# 05-General_I2C_Devices.net
KiCad netlist of a schematic drawn in Altium Designer
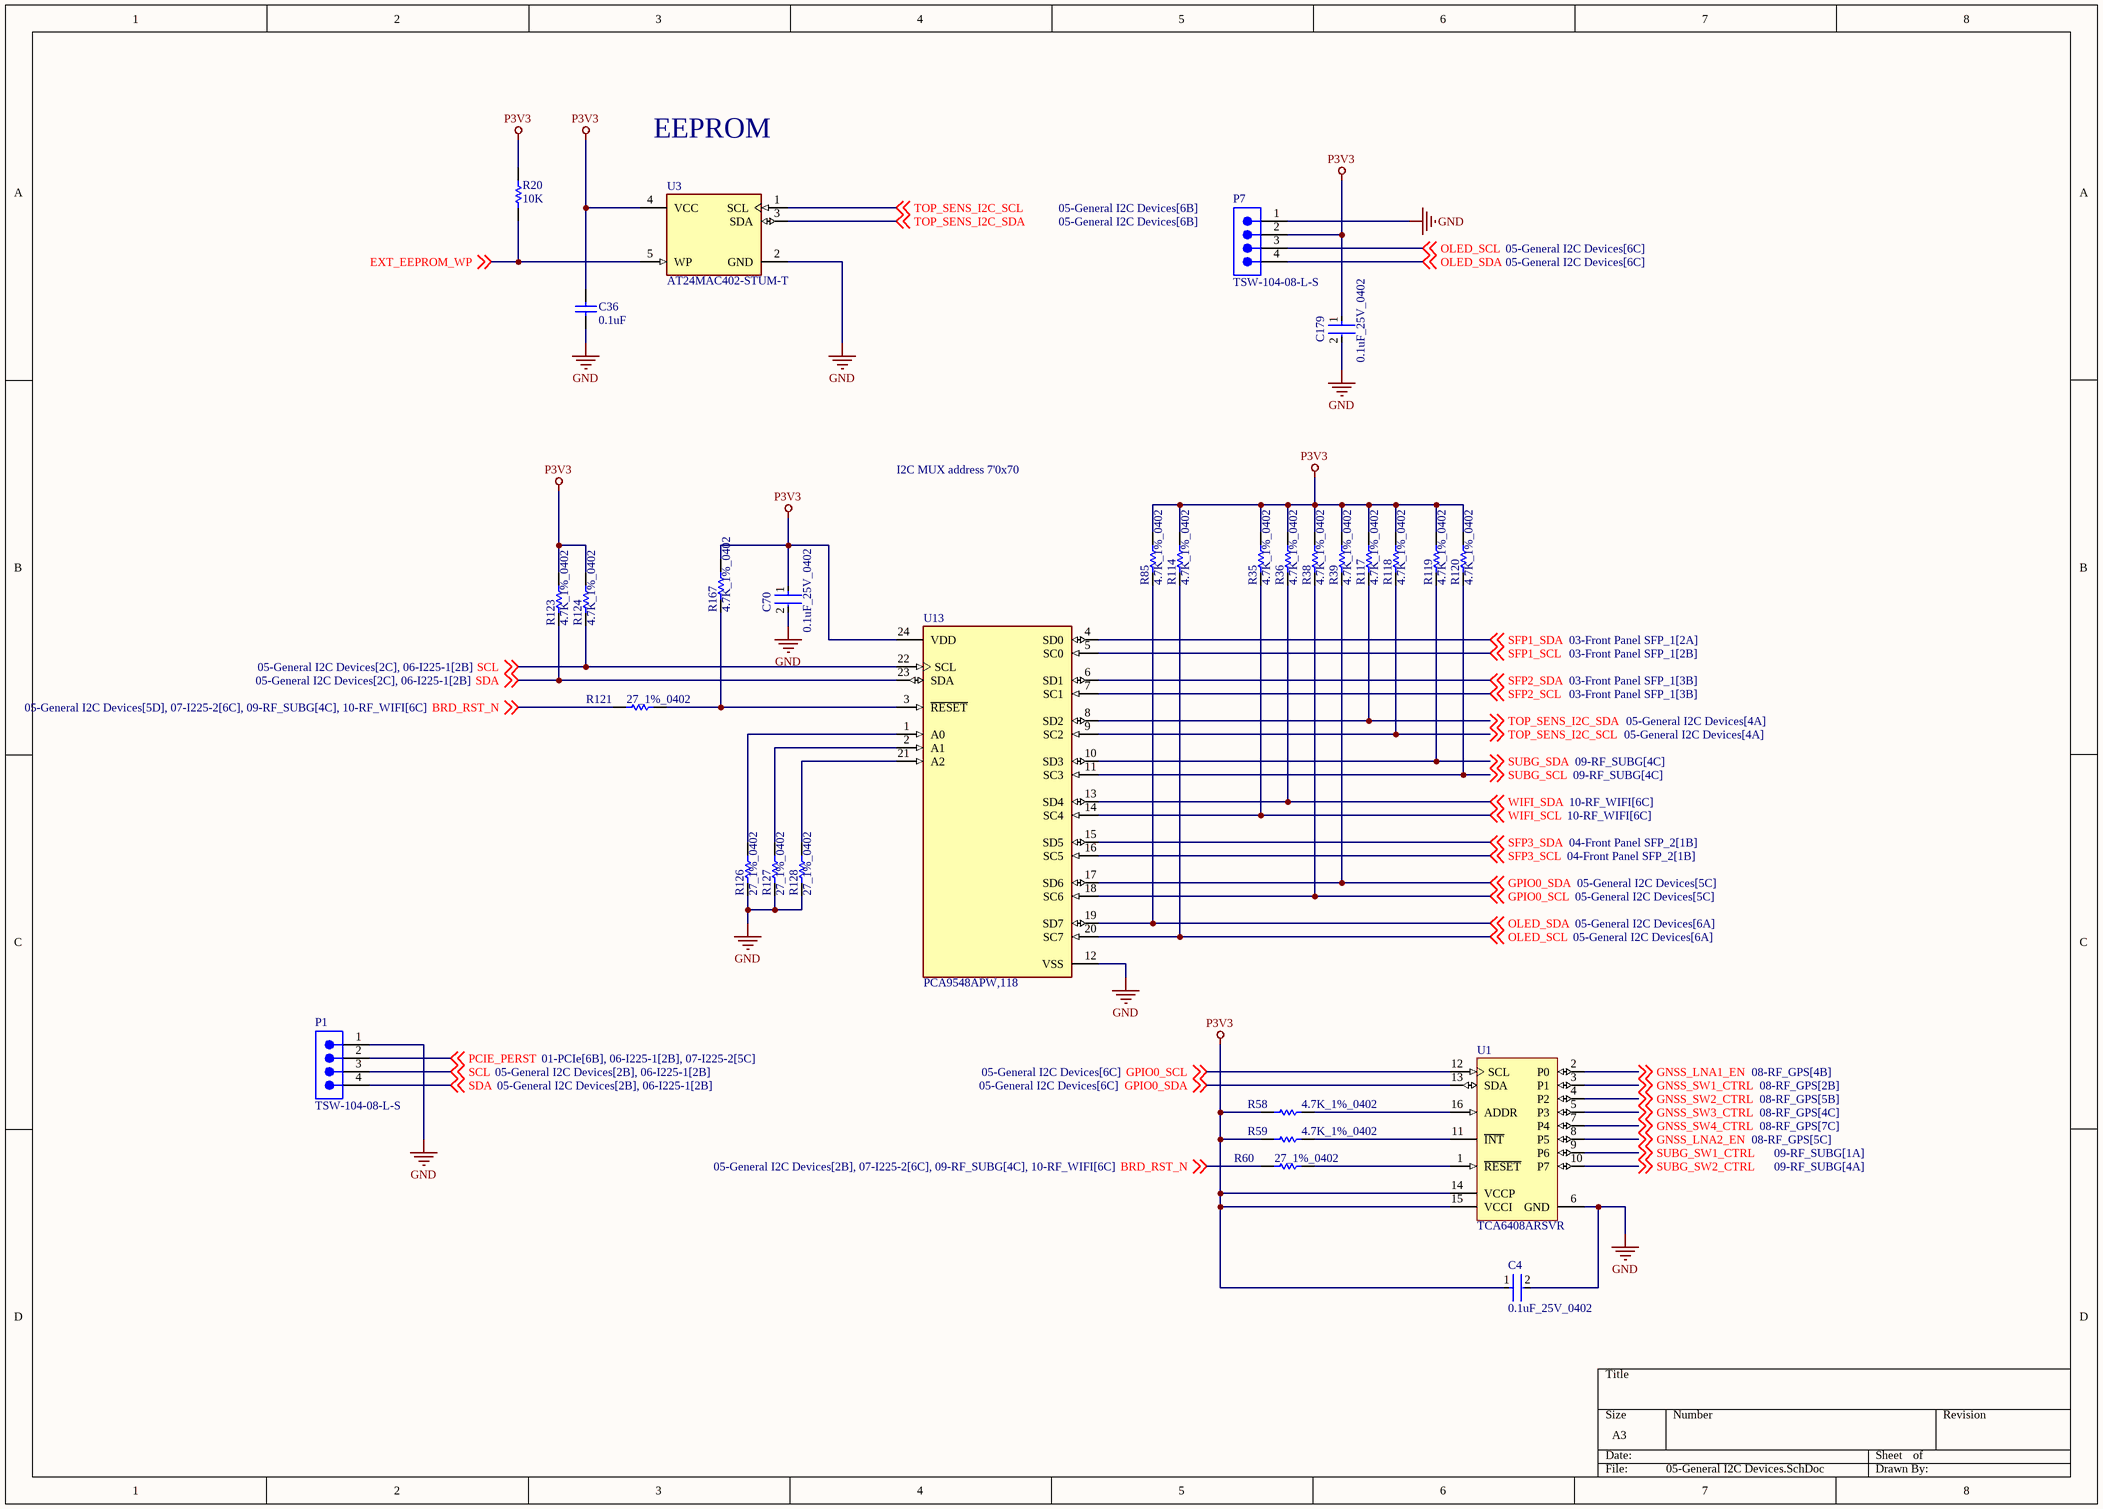
[diagram p0: 05-General I2C Devices.SchDoc]

(export (version "E")
  (design (tool "Eeschema 10.0.6"))
  (components
    (comp (ref "C4")
      (value "0.1uF_25V_0402")
      (footprint "FP-0402-L_1_0_1-W_0_5_0_1-IPC_C")
      (description "General Purpose Ceramic Capacitor, 0402, 100nF, 10%, X7R, 15%, 25V")
      (fields (field (name "VOLTAGE") "25V") (field (name "TOLERANCE") "10%"))
      (libsource (lib "Altium Content Vault") (part "b4654b650e69147ec39a6b967a45e02"))
    )
    (comp (ref "C36")
      (value "0.1uF")
      (footprint "CAPC1608X87X45ML20T05")
      (description "C0603X104K5RACAUTO")
      (fields (field (name "MANUFACTURER") "Kemet"))
      (libsource (lib "Altium Content Vault") (part "CAP"))
    )
    (comp (ref "C70")
      (value "0.1uF_25V_0402")
      (footprint "FP-0402-L_1_0_1-W_0_5_0_1-IPC_C")
      (description "General Purpose Ceramic Capacitor, 0402, 100nF, 10%, X7R, 15%, 25V")
      (fields (field (name "VOLTAGE") "25V") (field (name "TOLERANCE") "10%"))
      (libsource (lib "Altium Content Vault") (part "b4654b650e69147ec39a6b967a45e02"))
    )
    (comp (ref "C179")
      (value "0.1uF_25V_0402")
      (footprint "FP-0402-L_1_0_1-W_0_5_0_1-IPC_C")
      (description "General Purpose Ceramic Capacitor, 0402, 100nF, 10%, X7R, 15%, 25V")
      (fields (field (name "VOLTAGE") "25V") (field (name "TOLERANCE") "10%"))
      (libsource (lib "Altium Content Vault") (part "b4654b650e69147ec39a6b967a45e02"))
    )
    (comp (ref "P1")
      (value "TSW-104-08-L-S")
      (footprint "SMTC-TSW-104-08-X-S")
      (description "0.025\" SQ Post Header, Through-hole, Vertical, -55 to 125 degC, 2.54 mm Pitch, 4-Pin, Male, RoHS")
      (fields (field (name "MANUFACTURER") "Samtec"))
      (libsource (lib "Altium Content Vault") (part "SMTC-TSW-104-08-X-S"))
    )
    (comp (ref "P7")
      (value "TSW-104-08-L-S")
      (footprint "SMTC-TSW-104-08-X-S")
      (description "0.025\" SQ Post Header, Through-hole, Vertical, -55 to 125 degC, 2.54 mm Pitch, 4-Pin, Male, RoHS")
      (fields (field (name "MANUFACTURER") "Samtec"))
      (libsource (lib "Altium Content Vault") (part "SMTC-TSW-104-08-X-S"))
    )
    (comp (ref "R20")
      (value "10K")
      (footprint "RESC1608X55X30LL15T20")
      (fields (field (name "TOLERANCE") "±1%") (field (name "MANUFACTURER") "Stackpole-Electronics-Inc."))
      (libsource (lib "Altium Content Vault") (part "RES-2"))
    )
    (comp (ref "R35")
      (value "4.7K_1%_0402")
      (footprint "RESC1005X40X25NL10T10")
      (fields (field (name "MANUFACTURER") "Bourns") (field (name "PART NUMBER") "CR0402-FX-4701GLF"))
      (libsource (lib "Altium Content Vault") (part "RES"))
    )
    (comp (ref "R36")
      (value "4.7K_1%_0402")
      (footprint "RESC1005X40X25NL10T10")
      (fields (field (name "MANUFACTURER") "Bourns") (field (name "PART NUMBER") "CR0402-FX-4701GLF"))
      (libsource (lib "Altium Content Vault") (part "RES"))
    )
    (comp (ref "R38")
      (value "4.7K_1%_0402")
      (footprint "RESC1005X40X25NL10T10")
      (fields (field (name "MANUFACTURER") "Bourns") (field (name "PART NUMBER") "CR0402-FX-4701GLF"))
      (libsource (lib "Altium Content Vault") (part "RES"))
    )
    (comp (ref "R39")
      (value "4.7K_1%_0402")
      (footprint "RESC1005X40X25NL10T10")
      (fields (field (name "MANUFACTURER") "Bourns") (field (name "PART NUMBER") "CR0402-FX-4701GLF"))
      (libsource (lib "Altium Content Vault") (part "RES"))
    )
    (comp (ref "R58")
      (value "4.7K_1%_0402")
      (footprint "RESC1005X40X25NL10T10")
      (fields (field (name "MANUFACTURER") "Bourns") (field (name "PART NUMBER") "CR0402-FX-4701GLF"))
      (libsource (lib "Altium Content Vault") (part "RES"))
    )
    (comp (ref "R59")
      (value "4.7K_1%_0402")
      (footprint "RESC1005X40X25NL10T10")
      (fields (field (name "MANUFACTURER") "Bourns") (field (name "PART NUMBER") "CR0402-FX-4701GLF"))
      (libsource (lib "Altium Content Vault") (part "RES"))
    )
    (comp (ref "R60")
      (value "27_1%_0402")
      (footprint "RESC1005X40X25NL05T05")
      (fields (field (name "PART NUMBER") "CRCW040227R0FKED") (field (name "MANUFACTURER") "Vishay Dale"))
      (libsource (lib "Altium Content Vault") (part "RES"))
    )
    (comp (ref "R85")
      (value "4.7K_1%_0402")
      (footprint "RESC1005X40X25NL10T10")
      (fields (field (name "MANUFACTURER") "Bourns") (field (name "PART NUMBER") "CR0402-FX-4701GLF"))
      (libsource (lib "Altium Content Vault") (part "RES"))
    )
    (comp (ref "R114")
      (value "4.7K_1%_0402")
      (footprint "RESC1005X40X25NL10T10")
      (fields (field (name "MANUFACTURER") "Bourns") (field (name "PART NUMBER") "CR0402-FX-4701GLF"))
      (libsource (lib "Altium Content Vault") (part "RES"))
    )
    (comp (ref "R117")
      (value "4.7K_1%_0402")
      (footprint "RESC1005X40X25NL10T10")
      (fields (field (name "MANUFACTURER") "Bourns") (field (name "PART NUMBER") "CR0402-FX-4701GLF"))
      (libsource (lib "Altium Content Vault") (part "RES"))
    )
    (comp (ref "R118")
      (value "4.7K_1%_0402")
      (footprint "RESC1005X40X25NL10T10")
      (fields (field (name "MANUFACTURER") "Bourns") (field (name "PART NUMBER") "CR0402-FX-4701GLF"))
      (libsource (lib "Altium Content Vault") (part "RES"))
    )
    (comp (ref "R119")
      (value "4.7K_1%_0402")
      (footprint "RESC1005X40X25NL10T10")
      (fields (field (name "MANUFACTURER") "Bourns") (field (name "PART NUMBER") "CR0402-FX-4701GLF"))
      (libsource (lib "Altium Content Vault") (part "RES"))
    )
    (comp (ref "R120")
      (value "4.7K_1%_0402")
      (footprint "RESC1005X40X25NL10T10")
      (fields (field (name "MANUFACTURER") "Bourns") (field (name "PART NUMBER") "CR0402-FX-4701GLF"))
      (libsource (lib "Altium Content Vault") (part "RES"))
    )
    (comp (ref "R121")
      (value "27_1%_0402")
      (footprint "RESC1005X40X25NL05T05")
      (fields (field (name "PART NUMBER") "CRCW040227R0FKED") (field (name "MANUFACTURER") "Vishay Dale"))
      (libsource (lib "Altium Content Vault") (part "RES"))
    )
    (comp (ref "R123")
      (value "4.7K_1%_0402")
      (footprint "RESC1005X40X25NL10T10")
      (fields (field (name "MANUFACTURER") "Bourns") (field (name "PART NUMBER") "CR0402-FX-4701GLF"))
      (libsource (lib "Altium Content Vault") (part "RES"))
    )
    (comp (ref "R124")
      (value "4.7K_1%_0402")
      (footprint "RESC1005X40X25NL10T10")
      (fields (field (name "MANUFACTURER") "Bourns") (field (name "PART NUMBER") "CR0402-FX-4701GLF"))
      (libsource (lib "Altium Content Vault") (part "RES"))
    )
    (comp (ref "R126")
      (value "27_1%_0402")
      (footprint "RESC1005X40X25NL05T05")
      (fields (field (name "PART NUMBER") "CRCW040227R0FKED") (field (name "MANUFACTURER") "Vishay Dale"))
      (libsource (lib "Altium Content Vault") (part "RES"))
    )
    (comp (ref "R127")
      (value "27_1%_0402")
      (footprint "RESC1005X40X25NL05T05")
      (fields (field (name "PART NUMBER") "CRCW040227R0FKED") (field (name "MANUFACTURER") "Vishay Dale"))
      (libsource (lib "Altium Content Vault") (part "RES"))
    )
    (comp (ref "R128")
      (value "27_1%_0402")
      (footprint "RESC1005X40X25NL05T05")
      (fields (field (name "PART NUMBER") "CRCW040227R0FKED") (field (name "MANUFACTURER") "Vishay Dale"))
      (libsource (lib "Altium Content Vault") (part "RES"))
    )
    (comp (ref "R167")
      (value "4.7K_1%_0402")
      (footprint "RESC1005X40X25NL10T10")
      (fields (field (name "MANUFACTURER") "Bourns") (field (name "PART NUMBER") "CR0402-FX-4701GLF"))
      (libsource (lib "Altium Content Vault") (part "RES"))
    )
    (comp (ref "U1")
      (value "TCA6408ARSVR")
      (footprint "RSV0016A_V")
      (fields (field (name "MANUFACTURER") "Texas Instruments"))
      (libsource (lib "Altium Content Vault") (part "TI-TCA6408A-UQFN_RSV-16"))
    )
    (comp (ref "U3")
      (value "AT24MAC402-STUM-T")
      (footprint "FP-5TS1-IPC_C")
      (description "IC EEPROM 2K I2C 1MHZ SOT23-5")
      (fields
        (field (name "MANUFACTURER") "Microchip")
        (field (name "OCTOPART") "https://octopart.com/at24mac402-stum-t-microchip-77758112")
      )
      (libsource (lib "Altium Content Vault") (part "93fe34f5f049140596bab6421a6454b"))
    )
    (comp (ref "U13")
      (value "PCA9548APW,118")
      (footprint "FP-SOT355-1-MFG")
      (description "IC INTERFACE SPECIALIZED 24TSSOP")
      (libsource (lib "Altium Content Vault") (part "3e168d29e2cae1e9eb34f21911d2ccb"))
    )
  )
  (nets
    (net (code "1") (name "BRD_RST_N") (class "Default")
      (node (ref "R121") (pin "1") (pinfunction "1_1") (pintype "passive"))
      (node (ref "R60") (pin "1") (pinfunction "1_1") (pintype "passive"))
    )
    (net (code "2") (name "EXT_EEPROM_WP") (class "Default")
      (node (ref "R20") (pin "1") (pinfunction "1_1") (pintype "passive"))
      (node (ref "U3") (pin "5") (pinfunction "WP_5") (pintype "input"))
    )
    (net (code "3") (name "GND") (class "Default")
      (node (ref "C179") (pin "2") (pinfunction "2_2") (pintype "passive"))
      (node (ref "C36") (pin "1") (pinfunction "1_1") (pintype "passive"))
      (node (ref "C4") (pin "2") (pinfunction "2_2") (pintype "passive"))
      (node (ref "C70") (pin "2") (pinfunction "2_2") (pintype "passive"))
      (node (ref "P1") (pin "1") (pinfunction "1_1") (pintype "passive"))
      (node (ref "P7") (pin "1") (pinfunction "1_1") (pintype "passive"))
      (node (ref "R126") (pin "1") (pinfunction "1_1") (pintype "passive"))
      (node (ref "R127") (pin "1") (pinfunction "1_1") (pintype "passive"))
      (node (ref "R128") (pin "1") (pinfunction "1_1") (pintype "passive"))
      (node (ref "U1") (pin "6") (pinfunction "GND_6") (pintype "power_in"))
      (node (ref "U13") (pin "12") (pinfunction "VSS_12") (pintype "power_in"))
      (node (ref "U3") (pin "2") (pinfunction "GND_2") (pintype "power_in"))
    )
    (net (code "4") (name "GNSS_LNA1_EN") (class "Default")
      (node (ref "U1") (pin "2") (pinfunction "P0_2") (pintype "bidirectional"))
    )
    (net (code "5") (name "GNSS_LNA2_EN") (class "Default")
      (node (ref "U1") (pin "8") (pinfunction "P5_8") (pintype "bidirectional"))
    )
    (net (code "6") (name "GNSS_SW1_CTRL") (class "Default")
      (node (ref "U1") (pin "3") (pinfunction "P1_3") (pintype "bidirectional"))
    )
    (net (code "7") (name "GNSS_SW2_CTRL") (class "Default")
      (node (ref "U1") (pin "4") (pinfunction "P2_4") (pintype "bidirectional"))
    )
    (net (code "8") (name "GNSS_SW3_CTRL") (class "Default")
      (node (ref "U1") (pin "5") (pinfunction "P3_5") (pintype "bidirectional"))
    )
    (net (code "9") (name "GNSS_SW4_CTRL") (class "Default")
      (node (ref "U1") (pin "7") (pinfunction "P4_7") (pintype "bidirectional"))
    )
    (net (code "10") (name "GPIO0_SCL") (class "Default")
      (node (ref "R38") (pin "1") (pinfunction "1_1") (pintype "passive"))
      (node (ref "U1") (pin "12") (pinfunction "SCL_12") (pintype "input"))
      (node (ref "U13") (pin "18") (pinfunction "SC6_18") (pintype "input"))
    )
    (net (code "11") (name "GPIO0_SDA") (class "Default")
      (node (ref "R39") (pin "1") (pinfunction "1_1") (pintype "passive"))
      (node (ref "U1") (pin "13") (pinfunction "SDA_13") (pintype "bidirectional"))
      (node (ref "U13") (pin "17") (pinfunction "SD6_17") (pintype "bidirectional"))
    )
    (net (code "12") (name "Net-(U1-ADDR)") (class "Default")
      (node (ref "R58") (pin "1") (pinfunction "1_1") (pintype "passive"))
      (node (ref "U1") (pin "16") (pinfunction "ADDR_16") (pintype "input"))
    )
    (net (code "13") (name "Net-(U1-~{INT})") (class "Default")
      (node (ref "R59") (pin "1") (pinfunction "1_1") (pintype "passive"))
      (node (ref "U1") (pin "11") (pinfunction "~{INT}_11") (pintype "open_collector"))
    )
    (net (code "14") (name "Net-(U1-~{RESET})") (class "Default")
      (node (ref "R60") (pin "2") (pinfunction "2_2") (pintype "passive"))
      (node (ref "U1") (pin "1") (pinfunction "~{RESET}_1") (pintype "input"))
    )
    (net (code "15") (name "Net-(U13-A0)") (class "Default")
      (node (ref "R126") (pin "2") (pinfunction "2_2") (pintype "passive"))
      (node (ref "U13") (pin "1") (pinfunction "A0_1") (pintype "input"))
    )
    (net (code "16") (name "Net-(U13-A1)") (class "Default")
      (node (ref "R127") (pin "2") (pinfunction "2_2") (pintype "passive"))
      (node (ref "U13") (pin "2") (pinfunction "A1_2") (pintype "input"))
    )
    (net (code "17") (name "Net-(U13-A2)") (class "Default")
      (node (ref "R128") (pin "2") (pinfunction "2_2") (pintype "passive"))
      (node (ref "U13") (pin "21") (pinfunction "A2_21") (pintype "input"))
    )
    (net (code "18") (name "Net-(U13-~{RESET})") (class "Default")
      (node (ref "R121") (pin "2") (pinfunction "2_2") (pintype "passive"))
      (node (ref "R167") (pin "1") (pinfunction "1_1") (pintype "passive"))
      (node (ref "U13") (pin "3") (pinfunction "~{RESET}_3") (pintype "input"))
    )
    (net (code "19") (name "OLED_SCL") (class "Default")
      (node (ref "P7") (pin "3") (pinfunction "3_3") (pintype "passive"))
      (node (ref "R114") (pin "1") (pinfunction "1_1") (pintype "passive"))
      (node (ref "U13") (pin "20") (pinfunction "SC7_20") (pintype "input"))
    )
    (net (code "20") (name "OLED_SDA") (class "Default")
      (node (ref "P7") (pin "4") (pinfunction "4_4") (pintype "passive"))
      (node (ref "R85") (pin "1") (pinfunction "1_1") (pintype "passive"))
      (node (ref "U13") (pin "19") (pinfunction "SD7_19") (pintype "bidirectional"))
    )
    (net (code "21") (name "P3V3") (class "Default")
      (node (ref "C179") (pin "1") (pinfunction "1_1") (pintype "passive"))
      (node (ref "C36") (pin "2") (pinfunction "2_2") (pintype "passive"))
      (node (ref "C4") (pin "1") (pinfunction "1_1") (pintype "passive"))
      (node (ref "C70") (pin "1") (pinfunction "1_1") (pintype "passive"))
      (node (ref "P7") (pin "2") (pinfunction "2_2") (pintype "passive"))
      (node (ref "R114") (pin "2") (pinfunction "2_2") (pintype "passive"))
      (node (ref "R117") (pin "2") (pinfunction "2_2") (pintype "passive"))
      (node (ref "R118") (pin "2") (pinfunction "2_2") (pintype "passive"))
      (node (ref "R119") (pin "2") (pinfunction "2_2") (pintype "passive"))
      (node (ref "R120") (pin "2") (pinfunction "2_2") (pintype "passive"))
      (node (ref "R123") (pin "2") (pinfunction "2_2") (pintype "passive"))
      (node (ref "R124") (pin "2") (pinfunction "2_2") (pintype "passive"))
      (node (ref "R167") (pin "2") (pinfunction "2_2") (pintype "passive"))
      (node (ref "R20") (pin "2") (pinfunction "2_2") (pintype "passive"))
      (node (ref "R35") (pin "2") (pinfunction "2_2") (pintype "passive"))
      (node (ref "R36") (pin "2") (pinfunction "2_2") (pintype "passive"))
      (node (ref "R38") (pin "2") (pinfunction "2_2") (pintype "passive"))
      (node (ref "R39") (pin "2") (pinfunction "2_2") (pintype "passive"))
      (node (ref "R58") (pin "2") (pinfunction "2_2") (pintype "passive"))
      (node (ref "R59") (pin "2") (pinfunction "2_2") (pintype "passive"))
      (node (ref "R85") (pin "2") (pinfunction "2_2") (pintype "passive"))
      (node (ref "U1") (pin "14") (pinfunction "VCCP_14") (pintype "power_in"))
      (node (ref "U1") (pin "15") (pinfunction "VCCI_15") (pintype "power_in"))
      (node (ref "U13") (pin "24") (pinfunction "VDD_24") (pintype "power_in"))
      (node (ref "U3") (pin "4") (pinfunction "VCC_4") (pintype "power_in"))
    )
    (net (code "22") (name "PCIE_PERST") (class "Default")
      (node (ref "P1") (pin "2") (pinfunction "2_2") (pintype "passive"))
    )
    (net (code "23") (name "SCL") (class "Default")
      (node (ref "P1") (pin "3") (pinfunction "3_3") (pintype "passive"))
      (node (ref "R124") (pin "1") (pinfunction "1_1") (pintype "passive"))
      (node (ref "U13") (pin "22") (pinfunction "SCL_22") (pintype "input"))
    )
    (net (code "24") (name "SDA") (class "Default")
      (node (ref "P1") (pin "4") (pinfunction "4_4") (pintype "passive"))
      (node (ref "R123") (pin "1") (pinfunction "1_1") (pintype "passive"))
      (node (ref "U13") (pin "23") (pinfunction "SDA_23") (pintype "bidirectional"))
    )
    (net (code "25") (name "SFP1_SCL") (class "Default")
      (node (ref "U13") (pin "5") (pinfunction "SC0_5") (pintype "input"))
    )
    (net (code "26") (name "SFP1_SDA") (class "Default")
      (node (ref "U13") (pin "4") (pinfunction "SD0_4") (pintype "bidirectional"))
    )
    (net (code "27") (name "SFP2_SCL") (class "Default")
      (node (ref "U13") (pin "7") (pinfunction "SC1_7") (pintype "input"))
    )
    (net (code "28") (name "SFP2_SDA") (class "Default")
      (node (ref "U13") (pin "6") (pinfunction "SD1_6") (pintype "bidirectional"))
    )
    (net (code "29") (name "SFP3_SCL") (class "Default")
      (node (ref "U13") (pin "16") (pinfunction "SC5_16") (pintype "input"))
    )
    (net (code "30") (name "SFP3_SDA") (class "Default")
      (node (ref "U13") (pin "15") (pinfunction "SD5_15") (pintype "bidirectional"))
    )
    (net (code "31") (name "SUBG_SCL") (class "Default")
      (node (ref "R120") (pin "1") (pinfunction "1_1") (pintype "passive"))
      (node (ref "U13") (pin "11") (pinfunction "SC3_11") (pintype "input"))
    )
    (net (code "32") (name "SUBG_SDA") (class "Default")
      (node (ref "R119") (pin "1") (pinfunction "1_1") (pintype "passive"))
      (node (ref "U13") (pin "10") (pinfunction "SD3_10") (pintype "bidirectional"))
    )
    (net (code "33") (name "SUBG_SW1_CTRL") (class "Default")
      (node (ref "U1") (pin "9") (pinfunction "P6_9") (pintype "bidirectional"))
    )
    (net (code "34") (name "SUBG_SW2_CTRL") (class "Default")
      (node (ref "U1") (pin "10") (pinfunction "P7_10") (pintype "bidirectional"))
    )
    (net (code "35") (name "TOP_SENS_I2C_SCL") (class "Default")
      (node (ref "R118") (pin "1") (pinfunction "1_1") (pintype "passive"))
      (node (ref "U13") (pin "9") (pinfunction "SC2_9") (pintype "input"))
      (node (ref "U3") (pin "1") (pinfunction "SCL_1") (pintype "input"))
    )
    (net (code "36") (name "TOP_SENS_I2C_SDA") (class "Default")
      (node (ref "R117") (pin "1") (pinfunction "1_1") (pintype "passive"))
      (node (ref "U13") (pin "8") (pinfunction "SD2_8") (pintype "bidirectional"))
      (node (ref "U3") (pin "3") (pinfunction "SDA_3") (pintype "bidirectional"))
    )
    (net (code "37") (name "WIFI_SCL") (class "Default")
      (node (ref "R35") (pin "1") (pinfunction "1_1") (pintype "passive"))
      (node (ref "U13") (pin "14") (pinfunction "SC4_14") (pintype "input"))
    )
    (net (code "38") (name "WIFI_SDA") (class "Default")
      (node (ref "R36") (pin "1") (pinfunction "1_1") (pintype "passive"))
      (node (ref "U13") (pin "13") (pinfunction "SD4_13") (pintype "bidirectional"))
    )
  )
)
